# TX_v0.net
KiCad netlist of a schematic drawn in EAGLE
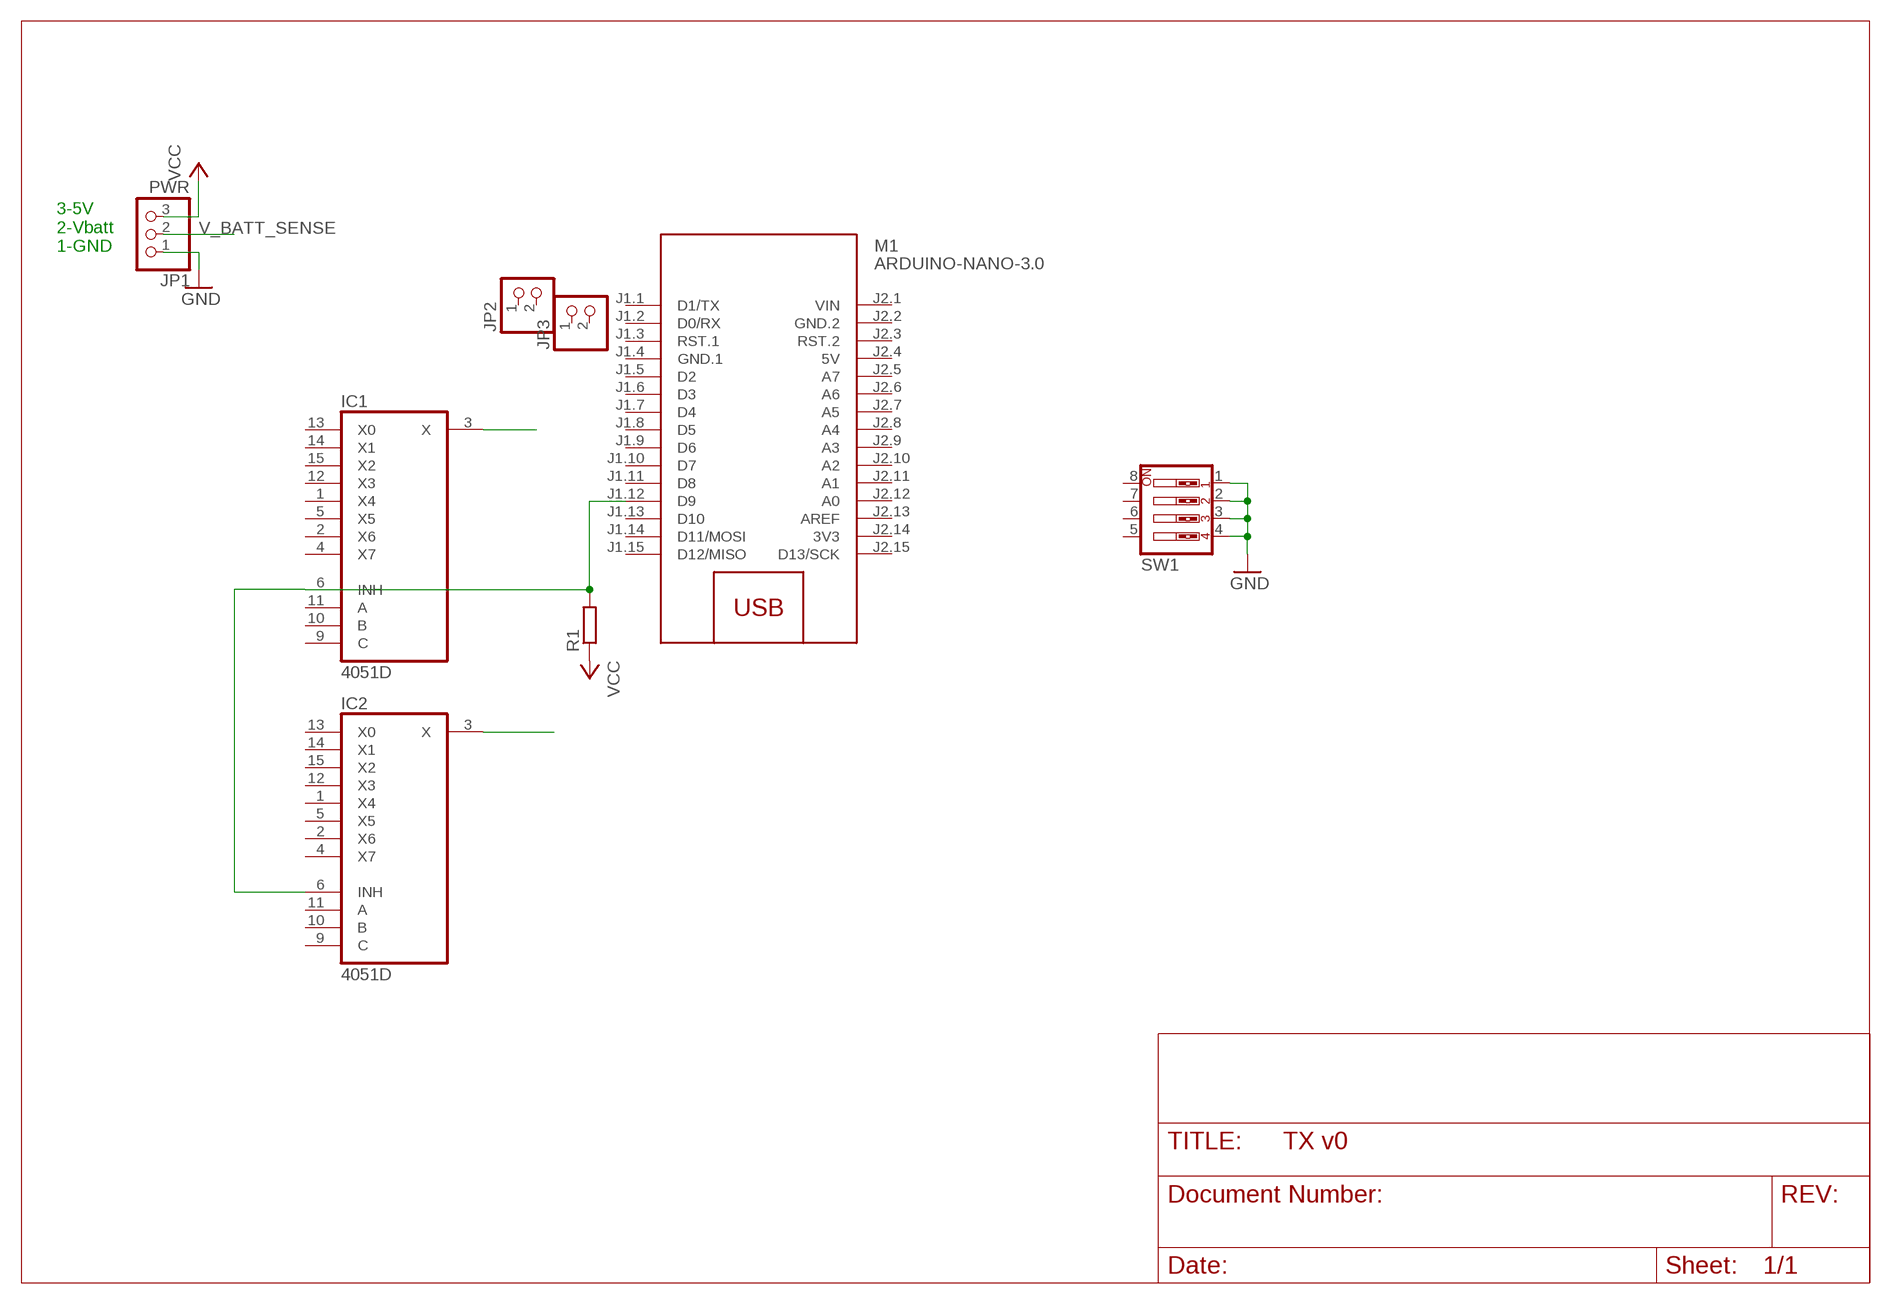
[diagram p0: schematic, sheet 1]

(export (version "E")
  (design (tool "Eeschema 10.0.6"))
  (components
    (comp (ref "IC1")
      (value "4051D")
      (footprint "eagle-import:SO16")
      (libsource (lib "eagle-import") (part "4051D"))
    )
    (comp (ref "IC2")
      (value "4051D")
      (footprint "eagle-import:SO16")
      (libsource (lib "eagle-import") (part "4051D"))
    )
    (comp (ref "JP1")
      (value "PWR")
      (footprint "eagle-import:1X03")
      (libsource (lib "eagle-import") (part "PINHD-1X3"))
    )
    (comp (ref "JP2")
      (value "PINHD-1X2")
      (footprint "eagle-import:1X02")
      (libsource (lib "eagle-import") (part "PINHD-1X2"))
    )
    (comp (ref "JP3")
      (value "PINHD-1X2")
      (footprint "eagle-import:1X02")
      (libsource (lib "eagle-import") (part "PINHD-1X2"))
    )
    (comp (ref "M1")
      (value "ARDUINO-NANO-3.0")
      (footprint "eagle-import:ARDUINO-NANO-3.0")
      (libsource (lib "eagle-import") (part "ARDUINO-NANO-3.0"))
    )
    (comp (ref "R1")
      (value "R-EU_0411/15")
      (footprint "eagle-import:0411_15")
      (libsource (lib "eagle-import") (part "R-EU_0411/15"))
    )
    (comp (ref "SW1")
      (value "SW_DIP-4")
      (footprint "eagle-import:EDG-04")
      (libsource (lib "eagle-import") (part "SW_DIP-4"))
    )
  )
  (nets
    (net (code "1") (name "/3V3") (class "Default")
      (node (ref "M1") (pin "J2.14") (pinfunction "3V3_J2.14") (pintype "power_in"))
    )
    (net (code "2") (name "/5V") (class "Default")
      (node (ref "M1") (pin "J2.4") (pinfunction "5V_J2.4") (pintype "power_in"))
    )
    (net (code "3") (name "/GND.1") (class "Default")
      (node (ref "M1") (pin "J1.4") (pinfunction "GND.1_J1.4") (pintype "power_in"))
    )
    (net (code "4") (name "/GND.2") (class "Default")
      (node (ref "M1") (pin "J2.2") (pinfunction "GND.2_J2.2") (pintype "power_in"))
    )
    (net (code "5") (name "/VIN") (class "Default")
      (node (ref "M1") (pin "J2.1") (pinfunction "VIN_J2.1") (pintype "power_in"))
    )
    (net (code "6") (name "/V_BATT_SENSE") (class "Default")
      (node (ref "JP1") (pin "2") (pinfunction "2_2") (pintype "passive"))
    )
    (net (code "7") (name "GND") (class "Default")
      (node (ref "JP1") (pin "1") (pinfunction "1_1") (pintype "passive"))
      (node (ref "SW1") (pin "1") (pinfunction "1_1") (pintype "passive"))
      (node (ref "SW1") (pin "2") (pinfunction "2_2") (pintype "passive"))
      (node (ref "SW1") (pin "3") (pinfunction "3_3") (pintype "passive"))
      (node (ref "SW1") (pin "4") (pinfunction "4_4") (pintype "passive"))
    )
    (net (code "8") (name "Net-(IC1A-INH)") (class "Default")
      (node (ref "IC1") (pin "6") (pinfunction "INH_6") (pintype "input"))
      (node (ref "IC2") (pin "6") (pinfunction "INH_6") (pintype "input"))
      (node (ref "M1") (pin "J1.12") (pinfunction "D9_J1.12") (pintype "bidirectional"))
      (node (ref "R1") (pin "2") (pinfunction "2_2") (pintype "passive"))
    )
    (net (code "9") (name "VCC") (class "Default")
      (node (ref "JP1") (pin "3") (pinfunction "3_3") (pintype "passive"))
      (node (ref "R1") (pin "1") (pinfunction "1_1") (pintype "passive"))
    )
    (net (code "10") (name "unconnected-(IC1A-A-Pad11)") (class "Default")
      (node (ref "IC1") (pin "11") (pinfunction "A_11") (pintype "input"))
    )
    (net (code "11") (name "unconnected-(IC1A-B-Pad10)") (class "Default")
      (node (ref "IC1") (pin "10") (pinfunction "B_10") (pintype "input"))
    )
    (net (code "12") (name "unconnected-(IC1A-C-Pad9)") (class "Default")
      (node (ref "IC1") (pin "9") (pinfunction "C_9") (pintype "input"))
    )
    (net (code "13") (name "unconnected-(IC1A-X-Pad3)") (class "Default")
      (node (ref "IC1") (pin "3") (pinfunction "X_3") (pintype "bidirectional"))
    )
    (net (code "14") (name "unconnected-(IC1A-X0-Pad13)") (class "Default")
      (node (ref "IC1") (pin "13") (pinfunction "X0_13") (pintype "bidirectional"))
    )
    (net (code "15") (name "unconnected-(IC1A-X1-Pad14)") (class "Default")
      (node (ref "IC1") (pin "14") (pinfunction "X1_14") (pintype "bidirectional"))
    )
    (net (code "16") (name "unconnected-(IC1A-X2-Pad15)") (class "Default")
      (node (ref "IC1") (pin "15") (pinfunction "X2_15") (pintype "bidirectional"))
    )
    (net (code "17") (name "unconnected-(IC1A-X3-Pad12)") (class "Default")
      (node (ref "IC1") (pin "12") (pinfunction "X3_12") (pintype "bidirectional"))
    )
    (net (code "18") (name "unconnected-(IC1A-X4-Pad1)") (class "Default")
      (node (ref "IC1") (pin "1") (pinfunction "X4_1") (pintype "bidirectional"))
    )
    (net (code "19") (name "unconnected-(IC1A-X5-Pad5)") (class "Default")
      (node (ref "IC1") (pin "5") (pinfunction "X5_5") (pintype "bidirectional"))
    )
    (net (code "20") (name "unconnected-(IC1A-X6-Pad2)") (class "Default")
      (node (ref "IC1") (pin "2") (pinfunction "X6_2") (pintype "bidirectional"))
    )
    (net (code "21") (name "unconnected-(IC1A-X7-Pad4)") (class "Default")
      (node (ref "IC1") (pin "4") (pinfunction "X7_4") (pintype "bidirectional"))
    )
    (net (code "22") (name "unconnected-(IC2A-A-Pad11)") (class "Default")
      (node (ref "IC2") (pin "11") (pinfunction "A_11") (pintype "input"))
    )
    (net (code "23") (name "unconnected-(IC2A-B-Pad10)") (class "Default")
      (node (ref "IC2") (pin "10") (pinfunction "B_10") (pintype "input"))
    )
    (net (code "24") (name "unconnected-(IC2A-C-Pad9)") (class "Default")
      (node (ref "IC2") (pin "9") (pinfunction "C_9") (pintype "input"))
    )
    (net (code "25") (name "unconnected-(IC2A-X-Pad3)") (class "Default")
      (node (ref "IC2") (pin "3") (pinfunction "X_3") (pintype "bidirectional"))
    )
    (net (code "26") (name "unconnected-(IC2A-X0-Pad13)") (class "Default")
      (node (ref "IC2") (pin "13") (pinfunction "X0_13") (pintype "bidirectional"))
    )
    (net (code "27") (name "unconnected-(IC2A-X1-Pad14)") (class "Default")
      (node (ref "IC2") (pin "14") (pinfunction "X1_14") (pintype "bidirectional"))
    )
    (net (code "28") (name "unconnected-(IC2A-X2-Pad15)") (class "Default")
      (node (ref "IC2") (pin "15") (pinfunction "X2_15") (pintype "bidirectional"))
    )
    (net (code "29") (name "unconnected-(IC2A-X3-Pad12)") (class "Default")
      (node (ref "IC2") (pin "12") (pinfunction "X3_12") (pintype "bidirectional"))
    )
    (net (code "30") (name "unconnected-(IC2A-X4-Pad1)") (class "Default")
      (node (ref "IC2") (pin "1") (pinfunction "X4_1") (pintype "bidirectional"))
    )
    (net (code "31") (name "unconnected-(IC2A-X5-Pad5)") (class "Default")
      (node (ref "IC2") (pin "5") (pinfunction "X5_5") (pintype "bidirectional"))
    )
    (net (code "32") (name "unconnected-(IC2A-X6-Pad2)") (class "Default")
      (node (ref "IC2") (pin "2") (pinfunction "X6_2") (pintype "bidirectional"))
    )
    (net (code "33") (name "unconnected-(IC2A-X7-Pad4)") (class "Default")
      (node (ref "IC2") (pin "4") (pinfunction "X7_4") (pintype "bidirectional"))
    )
    (net (code "34") (name "unconnected-(JP2-Pad1)") (class "Default")
      (node (ref "JP2") (pin "1") (pinfunction "1_1") (pintype "passive"))
    )
    (net (code "35") (name "unconnected-(JP2-Pad2)") (class "Default")
      (node (ref "JP2") (pin "2") (pinfunction "2_2") (pintype "passive"))
    )
    (net (code "36") (name "unconnected-(JP3-Pad1)") (class "Default")
      (node (ref "JP3") (pin "1") (pinfunction "1_1") (pintype "passive"))
    )
    (net (code "37") (name "unconnected-(JP3-Pad2)") (class "Default")
      (node (ref "JP3") (pin "2") (pinfunction "2_2") (pintype "passive"))
    )
    (net (code "38") (name "unconnected-(M1-A0-PadJ2.12)") (class "Default")
      (node (ref "M1") (pin "J2.12") (pinfunction "A0_J2.12") (pintype "bidirectional"))
    )
    (net (code "39") (name "unconnected-(M1-A1-PadJ2.11)") (class "Default")
      (node (ref "M1") (pin "J2.11") (pinfunction "A1_J2.11") (pintype "bidirectional"))
    )
    (net (code "40") (name "unconnected-(M1-A2-PadJ2.10)") (class "Default")
      (node (ref "M1") (pin "J2.10") (pinfunction "A2_J2.10") (pintype "bidirectional"))
    )
    (net (code "41") (name "unconnected-(M1-A3-PadJ2.9)") (class "Default")
      (node (ref "M1") (pin "J2.9") (pinfunction "A3_J2.9") (pintype "bidirectional"))
    )
    (net (code "42") (name "unconnected-(M1-A4-PadJ2.8)") (class "Default")
      (node (ref "M1") (pin "J2.8") (pinfunction "A4_J2.8") (pintype "bidirectional"))
    )
    (net (code "43") (name "unconnected-(M1-A5-PadJ2.7)") (class "Default")
      (node (ref "M1") (pin "J2.7") (pinfunction "A5_J2.7") (pintype "bidirectional"))
    )
    (net (code "44") (name "unconnected-(M1-A6-PadJ2.6)") (class "Default")
      (node (ref "M1") (pin "J2.6") (pinfunction "A6_J2.6") (pintype "bidirectional"))
    )
    (net (code "45") (name "unconnected-(M1-A7-PadJ2.5)") (class "Default")
      (node (ref "M1") (pin "J2.5") (pinfunction "A7_J2.5") (pintype "bidirectional"))
    )
    (net (code "46") (name "unconnected-(M1-AREF-PadJ2.13)") (class "Default")
      (node (ref "M1") (pin "J2.13") (pinfunction "AREF_J2.13") (pintype "bidirectional"))
    )
    (net (code "47") (name "unconnected-(M1-D0{slash}RX-PadJ1.2)") (class "Default")
      (node (ref "M1") (pin "J1.2") (pinfunction "D0/RX_J1.2") (pintype "bidirectional"))
    )
    (net (code "48") (name "unconnected-(M1-D1{slash}TX-PadJ1.1)") (class "Default")
      (node (ref "M1") (pin "J1.1") (pinfunction "D1/TX_J1.1") (pintype "bidirectional"))
    )
    (net (code "49") (name "unconnected-(M1-D2-PadJ1.5)") (class "Default")
      (node (ref "M1") (pin "J1.5") (pinfunction "D2_J1.5") (pintype "bidirectional"))
    )
    (net (code "50") (name "unconnected-(M1-D3-PadJ1.6)") (class "Default")
      (node (ref "M1") (pin "J1.6") (pinfunction "D3_J1.6") (pintype "bidirectional"))
    )
    (net (code "51") (name "unconnected-(M1-D4-PadJ1.7)") (class "Default")
      (node (ref "M1") (pin "J1.7") (pinfunction "D4_J1.7") (pintype "bidirectional"))
    )
    (net (code "52") (name "unconnected-(M1-D5-PadJ1.8)") (class "Default")
      (node (ref "M1") (pin "J1.8") (pinfunction "D5_J1.8") (pintype "bidirectional"))
    )
    (net (code "53") (name "unconnected-(M1-D6-PadJ1.9)") (class "Default")
      (node (ref "M1") (pin "J1.9") (pinfunction "D6_J1.9") (pintype "bidirectional"))
    )
    (net (code "54") (name "unconnected-(M1-D7-PadJ1.10)") (class "Default")
      (node (ref "M1") (pin "J1.10") (pinfunction "D7_J1.10") (pintype "bidirectional"))
    )
    (net (code "55") (name "unconnected-(M1-D8-PadJ1.11)") (class "Default")
      (node (ref "M1") (pin "J1.11") (pinfunction "D8_J1.11") (pintype "bidirectional"))
    )
    (net (code "56") (name "unconnected-(M1-D10-PadJ1.13)") (class "Default")
      (node (ref "M1") (pin "J1.13") (pinfunction "D10_J1.13") (pintype "bidirectional"))
    )
    (net (code "57") (name "unconnected-(M1-D11{slash}MOSI-PadJ1.14)") (class "Default")
      (node (ref "M1") (pin "J1.14") (pinfunction "D11/MOSI_J1.14") (pintype "bidirectional"))
    )
    (net (code "58") (name "unconnected-(M1-D12{slash}MISO-PadJ1.15)") (class "Default")
      (node (ref "M1") (pin "J1.15") (pinfunction "D12/MISO_J1.15") (pintype "bidirectional"))
    )
    (net (code "59") (name "unconnected-(M1-D13{slash}SCK-PadJ2.15)") (class "Default")
      (node (ref "M1") (pin "J2.15") (pinfunction "D13/SCK_J2.15") (pintype "bidirectional"))
    )
    (net (code "60") (name "unconnected-(M1-RST.1-PadJ1.3)") (class "Default")
      (node (ref "M1") (pin "J1.3") (pinfunction "RST.1_J1.3") (pintype "bidirectional"))
    )
    (net (code "61") (name "unconnected-(M1-RST.2-PadJ2.3)") (class "Default")
      (node (ref "M1") (pin "J2.3") (pinfunction "RST.2_J2.3") (pintype "bidirectional"))
    )
    (net (code "62") (name "unconnected-(SW1-Pad5)") (class "Default")
      (node (ref "SW1") (pin "5") (pinfunction "5_5") (pintype "passive"))
    )
    (net (code "63") (name "unconnected-(SW1-Pad6)") (class "Default")
      (node (ref "SW1") (pin "6") (pinfunction "6_6") (pintype "passive"))
    )
    (net (code "64") (name "unconnected-(SW1-Pad7)") (class "Default")
      (node (ref "SW1") (pin "7") (pinfunction "7_7") (pintype "passive"))
    )
    (net (code "65") (name "unconnected-(SW1-Pad8)") (class "Default")
      (node (ref "SW1") (pin "8") (pinfunction "8_8") (pintype "passive"))
    )
  )
)
